# Spectra6PCB_93.net
KiCad netlist of a schematic drawn in EAGLE
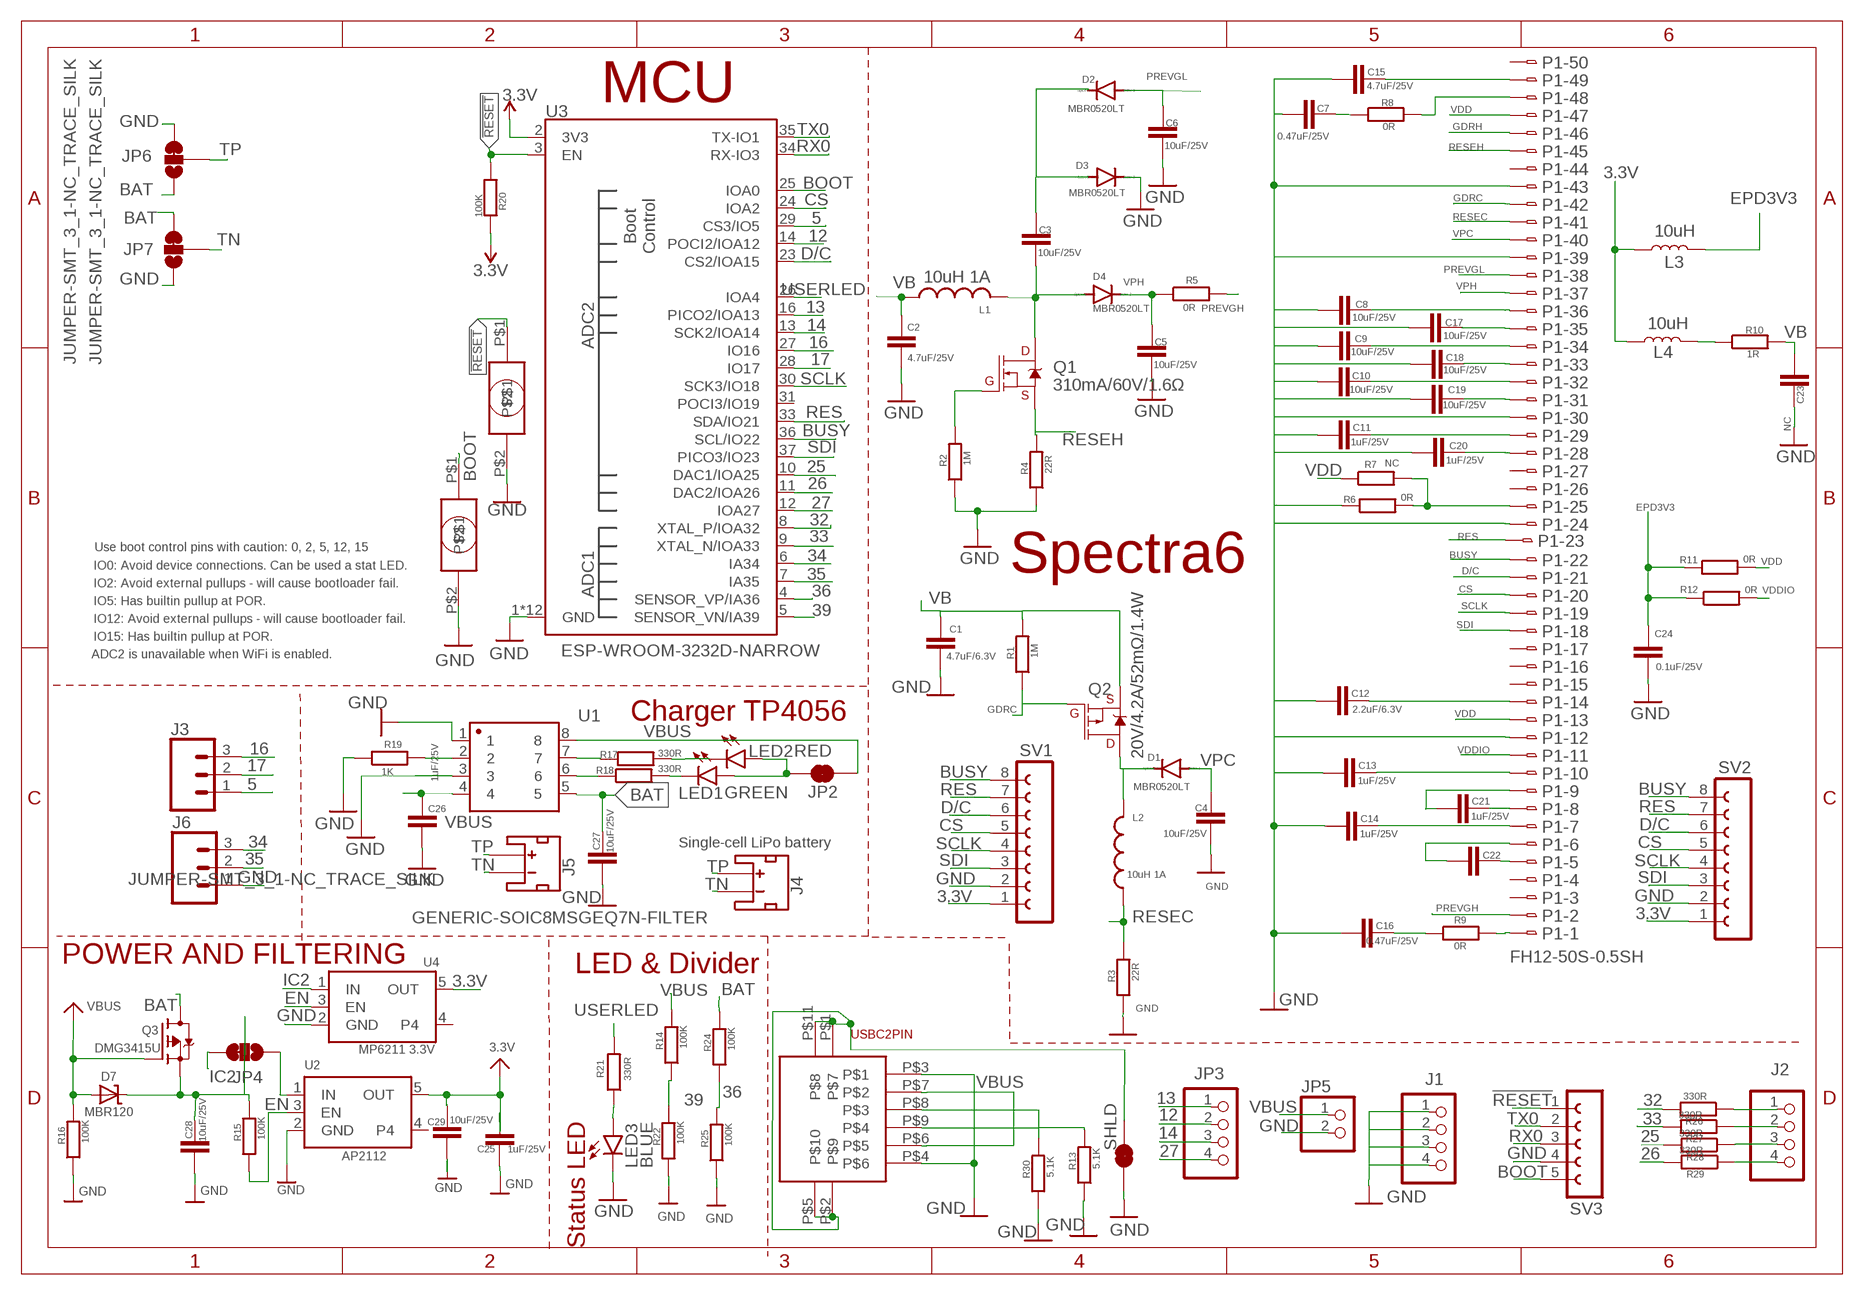
[diagram p0: schematic, sheet 1]

(export (version "E")
  (design (tool "Eeschema 10.0.6"))
  (components
    (comp (ref "C1")
      (value "4.7uF/6.3V")
      (footprint "eagle-import:C0805")
      (libsource (lib "eagle-import") (part "C-EUC0805"))
    )
    (comp (ref "C2")
      (value "4.7uF/25V")
      (footprint "eagle-import:C0805")
      (libsource (lib "eagle-import") (part "C-EUC0805"))
    )
    (comp (ref "C3")
      (value "10uF/25V")
      (footprint "eagle-import:C0805")
      (libsource (lib "eagle-import") (part "C-EUC0805"))
    )
    (comp (ref "C4")
      (value "10uF/25V")
      (footprint "eagle-import:C0805")
      (libsource (lib "eagle-import") (part "C-EUC0805"))
    )
    (comp (ref "C5")
      (value "10uF/25V")
      (footprint "eagle-import:C0805")
      (libsource (lib "eagle-import") (part "C-EUC0805"))
    )
    (comp (ref "C6")
      (value "10uF/25V")
      (footprint "eagle-import:C0805")
      (libsource (lib "eagle-import") (part "C-EUC0805"))
    )
    (comp (ref "C7")
      (value "0.47uF/25V")
      (footprint "eagle-import:C0805")
      (libsource (lib "eagle-import") (part "C-EUC0805"))
    )
    (comp (ref "C8")
      (value "10uF/25V")
      (footprint "eagle-import:C0805")
      (libsource (lib "eagle-import") (part "C-EUC0805"))
    )
    (comp (ref "C9")
      (value "10uF/25V")
      (footprint "eagle-import:C0805")
      (libsource (lib "eagle-import") (part "C-EUC0805"))
    )
    (comp (ref "C10")
      (value "10uF/25V")
      (footprint "eagle-import:C0805")
      (libsource (lib "eagle-import") (part "C-EUC0805"))
    )
    (comp (ref "C11")
      (value "1uF/25V")
      (footprint "eagle-import:C0805")
      (libsource (lib "eagle-import") (part "C-EUC0805"))
    )
    (comp (ref "C12")
      (value "2.2uF/6.3V")
      (footprint "eagle-import:C0805")
      (libsource (lib "eagle-import") (part "C-EUC0805"))
    )
    (comp (ref "C13")
      (value "1uF/25V")
      (footprint "eagle-import:C0805")
      (libsource (lib "eagle-import") (part "C-EUC0805"))
    )
    (comp (ref "C14")
      (value "1uF/25V")
      (footprint "eagle-import:C0805")
      (libsource (lib "eagle-import") (part "C-EUC0805"))
    )
    (comp (ref "C15")
      (value "4.7uF/25V")
      (footprint "eagle-import:C0805")
      (libsource (lib "eagle-import") (part "C-EUC0805"))
    )
    (comp (ref "C16")
      (value "0.47uF/25V")
      (footprint "eagle-import:C0805")
      (libsource (lib "eagle-import") (part "C-EUC0805"))
    )
    (comp (ref "C17")
      (value "10uF/25V")
      (footprint "eagle-import:C0805")
      (libsource (lib "eagle-import") (part "C-EUC0805"))
    )
    (comp (ref "C18")
      (value "10uF/25V")
      (footprint "eagle-import:C0805")
      (libsource (lib "eagle-import") (part "C-EUC0805"))
    )
    (comp (ref "C19")
      (value "10uF/25V")
      (footprint "eagle-import:C0805")
      (libsource (lib "eagle-import") (part "C-EUC0805"))
    )
    (comp (ref "C20")
      (value "1uF/25V")
      (footprint "eagle-import:C0805")
      (libsource (lib "eagle-import") (part "C-EUC0805"))
    )
    (comp (ref "C21")
      (value "1uF/25V")
      (footprint "eagle-import:C0805")
      (libsource (lib "eagle-import") (part "C-EUC0805"))
    )
    (comp (ref "C22")
      (value "1uF/25V")
      (footprint "eagle-import:C0805")
      (libsource (lib "eagle-import") (part "C-EUC0805"))
    )
    (comp (ref "C23")
      (value "NC")
      (footprint "eagle-import:C0805")
      (libsource (lib "eagle-import") (part "C-EUC0805"))
    )
    (comp (ref "C24")
      (value "0.1uF/25V")
      (footprint "eagle-import:C0805")
      (libsource (lib "eagle-import") (part "C-EUC0805"))
    )
    (comp (ref "C25")
      (value "1uF/25V")
      (footprint "eagle-import:C0805")
      (libsource (lib "eagle-import") (part "C-EUC0805"))
    )
    (comp (ref "C26")
      (value "1uF/25V")
      (footprint "eagle-import:C0805")
      (libsource (lib "eagle-import") (part "C-EUC0805"))
    )
    (comp (ref "C27")
      (value "10uF/25V")
      (footprint "eagle-import:C0805")
      (libsource (lib "eagle-import") (part "C-EUC0805"))
    )
    (comp (ref "C28")
      (value "10uF/25V")
      (footprint "eagle-import:C0805")
      (libsource (lib "eagle-import") (part "C-EUC0805"))
    )
    (comp (ref "C29")
      (value "10uF/25V")
      (footprint "eagle-import:C0805")
      (libsource (lib "eagle-import") (part "C-EUC0805"))
    )
    (comp (ref "D1")
      (value "MBR0520LT")
      (footprint "eagle-import:SOD123")
      (libsource (lib "eagle-import") (part "MBR0520LT"))
    )
    (comp (ref "D2")
      (value "MBR0520LT")
      (footprint "eagle-import:SOD123")
      (libsource (lib "eagle-import") (part "MBR0520LT"))
    )
    (comp (ref "D3")
      (value "MBR0520LT")
      (footprint "eagle-import:SOD123")
      (libsource (lib "eagle-import") (part "MBR0520LT"))
    )
    (comp (ref "D4")
      (value "MBR0520LT")
      (footprint "eagle-import:SOD123")
      (libsource (lib "eagle-import") (part "MBR0520LT"))
    )
    (comp (ref "D7")
      (value "MBR120")
      (footprint "eagle-import:SOD-123")
      (libsource (lib "eagle-import") (part "DIODE-SCHOTTKYSOD-123"))
    )
    (comp (ref "J1")
      (value "PINHD-1X4")
      (footprint "eagle-import:1X04")
      (libsource (lib "eagle-import") (part "PINHD-1X4"))
    )
    (comp (ref "J2")
      (value "PINHD-1X4")
      (footprint "eagle-import:1X04")
      (libsource (lib "eagle-import") (part "PINHD-1X4"))
    )
    (comp (ref "J3")
      (value "CONN_03PAD")
      (footprint "eagle-import:1X03_SOLDER_PADS")
      (libsource (lib "eagle-import") (part "CONN_03PAD"))
    )
    (comp (ref "J4")
      (value "JST_2MM_MALE")
      (footprint "eagle-import:JST-2-SMD")
      (libsource (lib "eagle-import") (part "JST_2MM_MALE"))
    )
    (comp (ref "J5")
      (value "NC")
      (footprint "eagle-import:JST-2-SMD")
      (libsource (lib "eagle-import") (part "JST_2MM_MALE"))
    )
    (comp (ref "J6")
      (value "CONN_03PAD")
      (footprint "eagle-import:1X03_SOLDER_PADS")
      (libsource (lib "eagle-import") (part "CONN_03PAD"))
    )
    (comp (ref "JP2")
      (value "JUMPER-SMT_2_NC_TRACE_SILK")
      (footprint "eagle-import:SMT-JUMPER_2_NC_TRACE_SILK")
      (libsource (lib "eagle-import") (part "JUMPER-SMT_2_NC_TRACE_SILK"))
    )
    (comp (ref "JP3")
      (value "PINHD-1X4")
      (footprint "eagle-import:1X04")
      (libsource (lib "eagle-import") (part "PINHD-1X4"))
    )
    (comp (ref "JP4")
      (value "JUMPER-SMT_3_1-NC_TRACE_SILK")
      (footprint "eagle-import:SMT-JUMPER_3_1-NC_TRACE_SILK")
      (libsource (lib "eagle-import") (part "JUMPER-SMT_3_1-NC_TRACE_SILK"))
    )
    (comp (ref "JP5")
      (value "PINHD-1X2")
      (footprint "eagle-import:1X02")
      (libsource (lib "eagle-import") (part "PINHD-1X2"))
    )
    (comp (ref "JP6")
      (value "JUMPER-SMT_3_1-NC_TRACE_SILK")
      (footprint "eagle-import:SMT-JUMPER_3_1-NC_TRACE_SILK")
      (libsource (lib "eagle-import") (part "JUMPER-SMT_3_1-NC_TRACE_SILK"))
    )
    (comp (ref "JP7")
      (value "JUMPER-SMT_3_1-NC_TRACE_SILK")
      (footprint "eagle-import:SMT-JUMPER_3_1-NC_TRACE_SILK")
      (libsource (lib "eagle-import") (part "JUMPER-SMT_3_1-NC_TRACE_SILK"))
    )
    (comp (ref "L1")
      (value "10uH 1A")
      (footprint "eagle-import:L4035M")
      (libsource (lib "eagle-import") (part "L-USL4035M"))
    )
    (comp (ref "L2")
      (value "10uH 1A")
      (footprint "eagle-import:L4035M")
      (libsource (lib "eagle-import") (part "L-USL4035M"))
    )
    (comp (ref "L3")
      (value "10uH")
      (footprint "eagle-import:0805")
      (libsource (lib "eagle-import") (part "INDUCTOR-0805-3.3UH"))
    )
    (comp (ref "L4")
      (value "10uH")
      (footprint "eagle-import:0805")
      (libsource (lib "eagle-import") (part "INDUCTOR-0805-3.3UH"))
    )
    (comp (ref "LED1")
      (value "GREEN")
      (footprint "eagle-import:SML0805")
      (libsource (lib "eagle-import") (part "LEDSML0805"))
    )
    (comp (ref "LED2")
      (value "RED")
      (footprint "eagle-import:SML0805")
      (libsource (lib "eagle-import") (part "LEDSML0805"))
    )
    (comp (ref "LED3")
      (value "BLUE")
      (footprint "eagle-import:SML0805")
      (libsource (lib "eagle-import") (part "LEDSML0805"))
    )
    (comp (ref "P1")
      (value "FH12-50S-0.5SH")
      (footprint "eagle-import:FH12-50S-0.5SH")
      (fields (field (name "MPN") "FH12-50S-0.5SH(55)"))
      (libsource (lib "eagle-import") (part "FH12-50S-0.5SH"))
    )
    (comp (ref "Q1")
      (value "310mA/60V/1.6Ω")
      (footprint "eagle-import:SOT323")
      (libsource (lib "eagle-import") (part "MOSFET-NCH-2N7002PW"))
    )
    (comp (ref "Q2")
      (value "20V/4.2A/52mΩ/1.4W")
      (footprint "eagle-import:SOT23-3")
      (libsource (lib "eagle-import") (part "MOSFET_PCH-DMG2305UX-7"))
    )
    (comp (ref "Q3")
      (value "DMG3415U")
      (footprint "eagle-import:SOT23-R")
      (libsource (lib "eagle-import") (part "MOSFET-P"))
    )
    (comp (ref "R1")
      (value "1M")
      (footprint "eagle-import:M0805")
      (libsource (lib "eagle-import") (part "R-EU_M0805"))
    )
    (comp (ref "R2")
      (value "1M")
      (footprint "eagle-import:M0805")
      (libsource (lib "eagle-import") (part "R-EU_M0805"))
    )
    (comp (ref "R3")
      (value "22R")
      (footprint "eagle-import:M0805")
      (libsource (lib "eagle-import") (part "R-EU_M0805"))
    )
    (comp (ref "R4")
      (value "22R")
      (footprint "eagle-import:M0805")
      (libsource (lib "eagle-import") (part "R-EU_M0805"))
    )
    (comp (ref "R5")
      (value "0R")
      (footprint "eagle-import:M0805")
      (libsource (lib "eagle-import") (part "R-EU_M0805"))
    )
    (comp (ref "R6")
      (value "0R")
      (footprint "eagle-import:M0805")
      (libsource (lib "eagle-import") (part "R-EU_M0805"))
    )
    (comp (ref "R7")
      (value "NC")
      (footprint "eagle-import:M0805")
      (libsource (lib "eagle-import") (part "R-EU_M0805"))
    )
    (comp (ref "R8")
      (value "0R")
      (footprint "eagle-import:M0805")
      (libsource (lib "eagle-import") (part "R-EU_M0805"))
    )
    (comp (ref "R9")
      (value "0R")
      (footprint "eagle-import:M0805")
      (libsource (lib "eagle-import") (part "R-EU_M0805"))
    )
    (comp (ref "R10")
      (value "1R")
      (footprint "eagle-import:M0805")
      (libsource (lib "eagle-import") (part "R-EU_M0805"))
    )
    (comp (ref "R11")
      (value "0R")
      (footprint "eagle-import:M0805")
      (libsource (lib "eagle-import") (part "R-EU_M0805"))
    )
    (comp (ref "R12")
      (value "0R")
      (footprint "eagle-import:M0805")
      (libsource (lib "eagle-import") (part "R-EU_M0805"))
    )
    (comp (ref "R13")
      (value "5.1K")
      (footprint "eagle-import:M0805")
      (libsource (lib "eagle-import") (part "R-EU_M0805"))
    )
    (comp (ref "R14")
      (value "100K")
      (footprint "eagle-import:M0805")
      (libsource (lib "eagle-import") (part "R-EU_M0805"))
    )
    (comp (ref "R15")
      (value "100K")
      (footprint "eagle-import:M0805")
      (libsource (lib "eagle-import") (part "R-EU_M0805"))
    )
    (comp (ref "R16")
      (value "100K")
      (footprint "eagle-import:M0805")
      (libsource (lib "eagle-import") (part "R-EU_M0805"))
    )
    (comp (ref "R17")
      (value "330R")
      (footprint "eagle-import:M0805")
      (libsource (lib "eagle-import") (part "R-EU_M0805"))
    )
    (comp (ref "R18")
      (value "330R")
      (footprint "eagle-import:M0805")
      (libsource (lib "eagle-import") (part "R-EU_M0805"))
    )
    (comp (ref "R19")
      (value "1K")
      (footprint "eagle-import:M0805")
      (libsource (lib "eagle-import") (part "R-EU_M0805"))
    )
    (comp (ref "R20")
      (value "100K")
      (footprint "eagle-import:M0805")
      (libsource (lib "eagle-import") (part "R-EU_M0805"))
    )
    (comp (ref "R21")
      (value "330R")
      (footprint "eagle-import:M0805")
      (libsource (lib "eagle-import") (part "R-EU_M0805"))
    )
    (comp (ref "R22")
      (value "100K")
      (footprint "eagle-import:M0805")
      (libsource (lib "eagle-import") (part "R-EU_M0805"))
    )
    (comp (ref "R24")
      (value "100K")
      (footprint "eagle-import:M0805")
      (libsource (lib "eagle-import") (part "R-EU_M0805"))
    )
    (comp (ref "R25")
      (value "100K")
      (footprint "eagle-import:M0805")
      (libsource (lib "eagle-import") (part "R-EU_M0805"))
    )
    (comp (ref "R26")
      (value "330R")
      (footprint "eagle-import:M0805")
      (libsource (lib "eagle-import") (part "R-EU_M0805"))
    )
    (comp (ref "R27")
      (value "330R")
      (footprint "eagle-import:M0805")
      (libsource (lib "eagle-import") (part "R-EU_M0805"))
    )
    (comp (ref "R28")
      (value "330R")
      (footprint "eagle-import:M0805")
      (libsource (lib "eagle-import") (part "R-EU_M0805"))
    )
    (comp (ref "R29")
      (value "330R")
      (footprint "eagle-import:M0805")
      (libsource (lib "eagle-import") (part "R-EU_M0805"))
    )
    (comp (ref "R30")
      (value "5.1K")
      (footprint "eagle-import:M0805")
      (libsource (lib "eagle-import") (part "R-EU_M0805"))
    )
    (comp (ref "S3")
      (value "TACTILE")
      (footprint "eagle-import:TACTILE")
      (libsource (lib "eagle-import") (part "TACTILE"))
    )
    (comp (ref "S4")
      (value "TACTILE")
      (footprint "eagle-import:TACTILE")
      (libsource (lib "eagle-import") (part "TACTILE"))
    )
    (comp (ref "SHLD")
      (value "SHLD")
      (footprint "eagle-import:SMT-JUMPER_2_NC_TRACE_NO-SILK")
      (libsource (lib "eagle-import") (part "JUMPER-SMT_2_NC_TRACE_NO-SILK"))
    )
    (comp (ref "SV1")
      (value "FE08-1")
      (footprint "eagle-import:FE08")
      (libsource (lib "eagle-import") (part "FE08-1"))
    )
    (comp (ref "SV2")
      (value "FE08-1")
      (footprint "eagle-import:FE08")
      (libsource (lib "eagle-import") (part "FE08-1"))
    )
    (comp (ref "SV3")
      (value "FE05-1")
      (footprint "eagle-import:FE05-1")
      (libsource (lib "eagle-import") (part "FE05-1"))
    )
    (comp (ref "U$4")
      (value "USBC6PIN")
      (footprint "eagle-import:USBC6PIN")
      (libsource (lib "eagle-import") (part "USBC6PIN"))
    )
    (comp (ref "U1")
      (value "GENERIC-SOIC8MSGEQ7N-FILTER")
      (footprint "eagle-import:SO08")
      (libsource (lib "eagle-import") (part "GENERIC-SOIC8MSGEQ7N-FILTER"))
    )
    (comp (ref "U2")
      (value "AP2112")
      (footprint "eagle-import:SOT23-5")
      (libsource (lib "eagle-import") (part "VREG_SOT23-5"))
    )
    (comp (ref "U3")
      (value "ESP-WROOM-3232D-NARROW")
      (footprint "eagle-import:ESP-WROOM-32D-NARROW")
      (libsource (lib "eagle-import") (part "ESP-WROOM-3232D-NARROW"))
    )
    (comp (ref "U4")
      (value "MP6211 3.3V")
      (footprint "eagle-import:SOT23-5")
      (libsource (lib "eagle-import") (part "VREG_SOT23-5"))
    )
  )
  (nets
    (net (code "1") (name "/5") (class "Default")
      (node (ref "J3") (pin "1") (pinfunction "1_1") (pintype "passive"))
      (node (ref "U3") (pin "29") (pinfunction "CS3/IO5_29") (pintype "bidirectional"))
    )
    (net (code "2") (name "/12") (class "Default")
      (node (ref "JP3") (pin "2") (pinfunction "2_2") (pintype "passive"))
      (node (ref "U3") (pin "14") (pinfunction "POCI2/IOA12_14") (pintype "bidirectional"))
    )
    (net (code "3") (name "/13") (class "Default")
      (node (ref "JP3") (pin "1") (pinfunction "1_1") (pintype "passive"))
      (node (ref "U3") (pin "16") (pinfunction "PICO2/IOA13_16") (pintype "bidirectional"))
    )
    (net (code "4") (name "/14") (class "Default")
      (node (ref "JP3") (pin "3") (pinfunction "3_3") (pintype "passive"))
      (node (ref "U3") (pin "13") (pinfunction "SCK2/IOA14_13") (pintype "bidirectional"))
    )
    (net (code "5") (name "/16") (class "Default")
      (node (ref "J3") (pin "3") (pinfunction "3_3") (pintype "passive"))
      (node (ref "U3") (pin "27") (pinfunction "IO16_27") (pintype "bidirectional"))
    )
    (net (code "6") (name "/17") (class "Default")
      (node (ref "J3") (pin "2") (pinfunction "2_2") (pintype "passive"))
      (node (ref "U3") (pin "28") (pinfunction "IO17_28") (pintype "bidirectional"))
    )
    (net (code "7") (name "/25") (class "Default")
      (node (ref "R28") (pin "2") (pinfunction "2_2") (pintype "passive"))
      (node (ref "U3") (pin "10") (pinfunction "DAC1/IOA25_10") (pintype "bidirectional"))
    )
    (net (code "8") (name "/26") (class "Default")
      (node (ref "R29") (pin "2") (pinfunction "2_2") (pintype "passive"))
      (node (ref "U3") (pin "11") (pinfunction "DAC2/IOA26_11") (pintype "bidirectional"))
    )
    (net (code "9") (name "/27") (class "Default")
      (node (ref "JP3") (pin "4") (pinfunction "4_4") (pintype "passive"))
      (node (ref "U3") (pin "12") (pinfunction "IOA27_12") (pintype "bidirectional"))
    )
    (net (code "10") (name "/32") (class "Default")
      (node (ref "R26") (pin "2") (pinfunction "2_2") (pintype "passive"))
      (node (ref "U3") (pin "8") (pinfunction "XTAL_P/IOA32_8") (pintype "bidirectional"))
    )
    (net (code "11") (name "/33") (class "Default")
      (node (ref "R27") (pin "2") (pinfunction "2_2") (pintype "passive"))
      (node (ref "U3") (pin "9") (pinfunction "XTAL_N/IOA33_9") (pintype "bidirectional"))
    )
    (net (code "12") (name "/34") (class "Default")
      (node (ref "J6") (pin "3") (pinfunction "3_3") (pintype "passive"))
      (node (ref "U3") (pin "6") (pinfunction "IA34_6") (pintype "bidirectional"))
    )
    (net (code "13") (name "/35") (class "Default")
      (node (ref "J6") (pin "2") (pinfunction "2_2") (pintype "passive"))
      (node (ref "U3") (pin "7") (pinfunction "IA35_7") (pintype "bidirectional"))
    )
    (net (code "14") (name "/36") (class "Default")
      (node (ref "R24") (pin "1") (pinfunction "1_1") (pintype "passive"))
      (node (ref "R25") (pin "2") (pinfunction "2_2") (pintype "passive"))
      (node (ref "U3") (pin "4") (pinfunction "SENSOR_VP/IA36_4") (pintype "bidirectional"))
    )
    (net (code "15") (name "/39") (class "Default")
      (node (ref "R14") (pin "1") (pinfunction "1_1") (pintype "passive"))
      (node (ref "R22") (pin "2") (pinfunction "2_2") (pintype "passive"))
      (node (ref "U3") (pin "5") (pinfunction "SENSOR_VN/IA39_5") (pintype "bidirectional"))
    )
    (net (code "16") (name "/BOOT") (class "Default")
      (node (ref "S3") (pin "P$1") (pinfunction "P$1_P$1") (pintype "bidirectional"))
      (node (ref "SV3") (pin "5") (pinfunction "5_5") (pintype "passive"))
      (node (ref "U3") (pin "25") (pinfunction "IOA0_25") (pintype "bidirectional"))
    )
    (net (code "17") (name "/BUSY") (class "Default")
      (node (ref "P1") (pin "22") (pinfunction "1_22") (pintype "passive"))
      (node (ref "SV1") (pin "8") (pinfunction "8_8") (pintype "passive"))
      (node (ref "SV2") (pin "8") (pinfunction "8_8") (pintype "passive"))
      (node (ref "U3") (pin "36") (pinfunction "SCL/IO22_36") (pintype "bidirectional"))
    )
    (net (code "18") (name "/CS") (class "Default")
      (node (ref "P1") (pin "20") (pinfunction "1_20") (pintype "passive"))
      (node (ref "SV1") (pin "5") (pinfunction "5_5") (pintype "passive"))
      (node (ref "SV2") (pin "5") (pinfunction "5_5") (pintype "passive"))
      (node (ref "U3") (pin "24") (pinfunction "IOA2_24") (pintype "bidirectional"))
    )
    (net (code "19") (name "/D{slash}C") (class "Default")
      (node (ref "P1") (pin "21") (pinfunction "1_21") (pintype "passive"))
      (node (ref "SV1") (pin "6") (pinfunction "6_6") (pintype "passive"))
      (node (ref "SV2") (pin "6") (pinfunction "6_6") (pintype "passive"))
      (node (ref "U3") (pin "23") (pinfunction "CS2/IOA15_23") (pintype "bidirectional"))
    )
    (net (code "20") (name "/EN") (class "Default")
      (node (ref "R15") (pin "1") (pinfunction "1_1") (pintype "passive"))
      (node (ref "U2") (pin "3") (pinfunction "EN_3") (pintype "input"))
      (node (ref "U4") (pin "3") (pinfunction "EN_3") (pintype "input"))
    )
    (net (code "21") (name "/EPD3V3") (class "Default")
      (node (ref "C24") (pin "2") (pinfunction "2_2") (pintype "passive"))
      (node (ref "L3") (pin "2") (pinfunction "2_2") (pintype "passive"))
      (node (ref "R11") (pin "1") (pinfunction "1_1") (pintype "passive"))
      (node (ref "R12") (pin "1") (pinfunction "1_1") (pintype "passive"))
    )
    (net (code "22") (name "/GDRC") (class "Default")
      (node (ref "P1") (pin "42") (pinfunction "1_42") (pintype "passive"))
      (node (ref "Q2") (pin "1") (pinfunction "G_1") (pintype "bidirectional"))
      (node (ref "R1") (pin "1") (pinfunction "1_1") (pintype "passive"))
    )
    (net (code "23") (name "/GDRH") (class "Default")
      (node (ref "P1") (pin "46") (pinfunction "1_46") (pintype "passive"))
      (node (ref "Q1") (pin "1") (pinfunction "G_1") (pintype "bidirectional"))
      (node (ref "R2") (pin "2") (pinfunction "2_2") (pintype "passive"))
    )
    (net (code "24") (name "/IC2") (class "Default")
      (node (ref "JP4") (pin "3") (pinfunction "3_3") (pintype "passive"))
      (node (ref "U4") (pin "1") (pinfunction "IN_1") (pintype "power_in"))
    )
    (net (code "25") (name "/PREVGH") (class "Default")
      (node (ref "P1") (pin "2") (pinfunction "1_2") (pintype "passive"))
      (node (ref "R5") (pin "2") (pinfunction "2_2") (pintype "passive"))
    )
    (net (code "26") (name "/PREVGL") (class "Default")
      (node (ref "C6") (pin "1") (pinfunction "1_1") (pintype "passive"))
      (node (ref "D2") (pin "A") (pinfunction "A_A") (pintype "passive"))
      (node (ref "P1") (pin "38") (pinfunction "1_38") (pintype "passive"))
    )
    (net (code "27") (name "/RES") (class "Default")
      (node (ref "P1") (pin "23") (pinfunction "1_23") (pintype "passive"))
      (node (ref "SV1") (pin "7") (pinfunction "7_7") (pintype "passive"))
      (node (ref "SV2") (pin "7") (pinfunction "7_7") (pintype "passive"))
      (node (ref "U3") (pin "33") (pinfunction "SDA/IO21_33") (pintype "bidirectional"))
    )
    (net (code "28") (name "/RESEC") (class "Default")
      (node (ref "L2") (pin "1") (pinfunction "1_1") (pintype "passive"))
      (node (ref "P1") (pin "41") (pinfunction "1_41") (pintype "passive"))
      (node (ref "R3") (pin "2") (pinfunction "2_2") (pintype "passive"))
    )
    (net (code "29") (name "/RESEH") (class "Default")
      (node (ref "P1") (pin "45") (pinfunction "1_45") (pintype "passive"))
      (node (ref "Q1") (pin "2") (pinfunction "S_2") (pintype "bidirectional"))
      (node (ref "R4") (pin "2") (pinfunction "2_2") (pintype "passive"))
    )
    (net (code "30") (name "/RX0") (class "Default")
      (node (ref "SV3") (pin "3") (pinfunction "3_3") (pintype "passive"))
      (node (ref "U3") (pin "34") (pinfunction "RX-IO3_34") (pintype "bidirectional"))
    )
    (net (code "31") (name "/SCLK") (class "Default")
      (node (ref "P1") (pin "19") (pinfunction "1_19") (pintype "passive"))
      (node (ref "SV1") (pin "4") (pinfunction "4_4") (pintype "passive"))
      (node (ref "SV2") (pin "4") (pinfunction "4_4") (pintype "passive"))
      (node (ref "U3") (pin "30") (pinfunction "SCK3/IO18_30") (pintype "bidirectional"))
    )
    (net (code "32") (name "/SDI") (class "Default")
      (node (ref "P1") (pin "18") (pinfunction "1_18") (pintype "passive"))
      (node (ref "SV1") (pin "3") (pinfunction "3_3") (pintype "passive"))
      (node (ref "SV2") (pin "3") (pinfunction "3_3") (pintype "passive"))
      (node (ref "U3") (pin "37") (pinfunction "PICO3/IO23_37") (pintype "bidirectional"))
    )
    (net (code "33") (name "/TN") (class "Default")
      (node (ref "J4") (pin "1") (pinfunction "-_1") (pintype "bidirectional"))
      (node (ref "J5") (pin "1") (pinfunction "-_1") (pintype "bidirectional"))
      (node (ref "JP7") (pin "2") (pinfunction "2_2") (pintype "passive"))
    )
    (net (code "34") (name "/TP") (class "Default")
      (node (ref "J4") (pin "2") (pinfunction "+_2") (pintype "bidirectional"))
      (node (ref "J5") (pin "2") (pinfunction "+_2") (pintype "bidirectional"))
      (node (ref "JP6") (pin "2") (pinfunction "2_2") (pintype "passive"))
    )
    (net (code "35") (name "/TX0") (class "Default")
      (node (ref "SV3") (pin "2") (pinfunction "2_2") (pintype "passive"))
      (node (ref "U3") (pin "35") (pinfunction "TX-IO1_35") (pintype "bidirectional"))
    )
    (net (code "36") (name "/USERLED") (class "Default")
      (node (ref "R21") (pin "2") (pinfunction "2_2") (pintype "passive"))
      (node (ref "U3") (pin "26") (pinfunction "IOA4_26") (pintype "bidirectional"))
    )
    (net (code "37") (name "/VB") (class "Default")
      (node (ref "C2") (pin "2") (pinfunction "2_2") (pintype "passive"))
      (node (ref "C23") (pin "1") (pinfunction "1_1") (pintype "passive"))
      (node (ref "L1") (pin "1") (pinfunction "1_1") (pintype "passive"))
      (node (ref "R10") (pin "2") (pinfunction "2_2") (pintype "passive"))
    )
    (net (code "38") (name "/VDD") (class "Default")
      (node (ref "P1") (pin "13") (pinfunction "1_13") (pintype "passive"))
      (node (ref "P1") (pin "47") (pinfunction "1_47") (pintype "passive"))
      (node (ref "R11") (pin "2") (pinfunction "2_2") (pintype "passive"))
      (node (ref "R7") (pin "1") (pinfunction "1_1") (pintype "passive"))
    )
    (net (code "39") (name "/VDDIO") (class "Default")
      (node (ref "P1") (pin "11") (pinfunction "1_11") (pintype "passive"))
      (node (ref "R12") (pin "2") (pinfunction "2_2") (pintype "passive"))
    )
    (net (code "40") (name "/VPC") (class "Default")
      (node (ref "C4") (pin "2") (pinfunction "2_2") (pintype "passive"))
      (node (ref "D1") (pin "A") (pinfunction "A_A") (pintype "passive"))
      (node (ref "P1") (pin "40") (pinfunction "1_40") (pintype "passive"))
    )
    (net (code "41") (name "/VPH") (class "Default")
      (node (ref "C5") (pin "1") (pinfunction "1_1") (pintype "passive"))
      (node (ref "D4") (pin "C") (pinfunction "C_C") (pintype "passive"))
      (node (ref "P1") (pin "37") (pinfunction "1_37") (pintype "passive"))
      (node (ref "R5") (pin "1") (pinfunction "1_1") (pintype "passive"))
    )
    (net (code "42") (name "/~{RESET}") (class "Default")
      (node (ref "R20") (pin "1") (pinfunction "1_1") (pintype "passive"))
      (node (ref "S4") (pin "P$1") (pinfunction "P$1_P$1") (pintype "bidirectional"))
      (node (ref "SV3") (pin "1") (pinfunction "1_1") (pintype "passive"))
      (node (ref "U3") (pin "3") (pinfunction "EN_3") (pintype "bidirectional"))
    )
    (net (code "43") (name "3.3V") (class "Default")
      (node (ref "C25") (pin "2") (pinfunction "2_2") (pintype "passive"))
      (node (ref "C29") (pin "2") (pinfunction "2_2") (pintype "passive"))
      (node (ref "L3") (pin "1") (pinfunction "1_1") (pintype "passive"))
      (node (ref "L4") (pin "1") (pinfunction "1_1") (pintype "passive"))
      (node (ref "R20") (pin "2") (pinfunction "2_2") (pintype "passive"))
      (node (ref "SV1") (pin "1") (pinfunction "1_1") (pintype "passive"))
      (node (ref "SV2") (pin "1") (pinfunction "1_1") (pintype "passive"))
      (node (ref "U2") (pin "5") (pinfunction "OUT_5") (pintype "power_in"))
      (node (ref "U3") (pin "2") (pinfunction "3V3_2") (pintype "bidirectional"))
      (node (ref "U4") (pin "5") (pinfunction "OUT_5") (pintype "power_in"))
    )
    (net (code "44") (name "BAT") (class "Default")
      (node (ref "C27") (pin "2") (pinfunction "2_2") (pintype "passive"))
      (node (ref "JP6") (pin "1") (pinfunction "1_1") (pintype "passive"))
      (node (ref "JP7") (pin "3") (pinfunction "3_3") (pintype "passive"))
      (node (ref "Q3") (pin "3") (pinfunction "D_3") (pintype "passive"))
      (node (ref "R24") (pin "2") (pinfunction "2_2") (pintype "passive"))
      (node (ref "U1") (pin "5") (pinfunction "5_5") (pintype "bidirectional"))
    )
    (net (code "45") (name "GND") (class "Default")
      (node (ref "C1") (pin "1") (pinfunction "1_1") (pintype "passive"))
      (node (ref "C10") (pin "1") (pinfunction "1_1") (pintype "passive"))
      (node (ref "C11") (pin "1") (pinfunction "1_1") (pintype "passive"))
      (node (ref "C12") (pin "1") (pinfunction "1_1") (pintype "passive"))
      (node (ref "C13") (pin "1") (pinfunction "1_1") (pintype "passive"))
      (node (ref "C14") (pin "1") (pinfunction "1_1") (pintype "passive"))
      (node (ref "C15") (pin "1") (pinfunction "1_1") (pintype "passive"))
      (node (ref "C16") (pin "1") (pinfunction "1_1") (pintype "passive"))
      (node (ref "C17") (pin "1") (pinfunction "1_1") (pintype "passive"))
      (node (ref "C18") (pin "1") (pinfunction "1_1") (pintype "passive"))
      (node (ref "C19") (pin "1") (pinfunction "1_1") (pintype "passive"))
      (node (ref "C2") (pin "1") (pinfunction "1_1") (pintype "passive"))
      (node (ref "C20") (pin "1") (pinfunction "1_1") (pintype "passive"))
      (node (ref "C23") (pin "2") (pinfunction "2_2") (pintype "passive"))
      (node (ref "C24") (pin "1") (pinfunction "1_1") (pintype "passive"))
      (node (ref "C25") (pin "1") (pinfunction "1_1") (pintype "passive"))
      (node (ref "C26") (pin "1") (pinfunction "1_1") (pintype "passive"))
      (node (ref "C27") (pin "1") (pinfunction "1_1") (pintype "passive"))
      (node (ref "C28") (pin "1") (pinfunction "1_1") (pintype "passive"))
      (node (ref "C29") (pin "1") (pinfunction "1_1") (pintype "passive"))
      (node (ref "C4") (pin "1") (pinfunction "1_1") (pintype "passive"))
      (node (ref "C5") (pin "2") (pinfunction "2_2") (pintype "passive"))
      (node (ref "C6") (pin "2") (pinfunction "2_2") (pintype "passive"))
      (node (ref "C7") (pin "1") (pinfunction "1_1") (pintype "passive"))
      (node (ref "C8") (pin "1") (pinfunction "1_1") (pintype "passive"))
      (node (ref "C9") (pin "1") (pinfunction "1_1") (pintype "passive"))
      (node (ref "D3") (pin "C") (pinfunction "C_C") (pintype "passive"))
      (node (ref "J1") (pin "1") (pinfunction "1_1") (pintype "passive"))
      (node (ref "J1") (pin "2") (pinfunction "2_2") (pintype "passive"))
      (node (ref "J1") (pin "3") (pinfunction "3_3") (pintype "passive"))
      (node (ref "J1") (pin "4") (pinfunction "4_4") (pintype "passive"))
      (node (ref "J6") (pin "1") (pinfunction "1_1") (pintype "passive"))
      (node (ref "JP5") (pin "2") (pinfunction "2_2") (pintype "passive"))
      (node (ref "JP6") (pin "3") (pinfunction "3_3") (pintype "passive"))
      (node (ref "JP7") (pin "1") (pinfunction "1_1") (pintype "passive"))
      (node (ref "LED3") (pin "C") (pinfunction "C_C") (pintype "passive"))
      (node (ref "P1") (pin "24") (pinfunction "1_24") (pintype "passive"))
      (node (ref "P1") (pin "30") (pinfunction "1_30") (pintype "passive"))
      (node (ref "P1") (pin "39") (pinfunction "1_39") (pintype "passive"))
      (node (ref "P1") (pin "43") (pinfunction "1_43") (pintype "passive"))
      (node (ref "R13") (pin "1") (pinfunction "1_1") (pintype "passive"))
      (node (ref "R16") (pin "1") (pinfunction "1_1") (pintype "passive"))
      (node (ref "R19") (pin "1") (pinfunction "1_1") (pintype "passive"))
      (node (ref "R2") (pin "1") (pinfunction "1_1") (pintype "passive"))
      (node (ref "R22") (pin "1") (pinfunction "1_1") (pintype "passive"))
      (node (ref "R25") (pin "1") (pinfunction "1_1") (pintype "passive"))
      (node (ref "R3") (pin "1") (pinfunction "1_1") (pintype "passive"))
      (node (ref "R30") (pin "1") (pinfunction "1_1") (pintype "passive"))
      (node (ref "R4") (pin "1") (pinfunction "1_1") (pintype "passive"))
      (node (ref "R6") (pin "1") (pinfunction "1_1") (pintype "passive"))
      (node (ref "S3") (pin "P$2") (pinfunction "P$2_P$2") (pintype "bidirectional"))
      (node (ref "S4") (pin "P$2") (pinfunction "P$2_P$2") (pintype "bidirectional"))
      (node (ref "SHLD") (pin "1") (pinfunction "1_1") (pintype "passive"))
      (node (ref "SV1") (pin "2") (pinfunction "2_2") (pintype "passive"))
      (node (ref "SV2") (pin "2") (pinfunction "2_2") (pintype "passive"))
      (node (ref "SV3") (pin "4") (pinfunction "4_4") (pintype "passive"))
      (node (ref "U$4") (pin "P$3") (pinfunction "P$1_P$3") (pintype "bidirectional"))
      (node (ref "U$4") (pin "P$4") (pinfunction "P$6_P$4") (pintype "bidirectional"))
      (node (ref "U1") (pin "1") (pinfunction "1_1") (pintype "bidirectional"))
      (node (ref "U1") (pin "3") (pinfunction "3_3") (pintype "bidirectional"))
      (node (ref "U2") (pin "2") (pinfunction "GND_2") (pintype "power_in"))
      (node (ref "U3") (pin "1") (pinfunction "GND_1") (pintype "bidirectional"))
      (node (ref "U3") (pin "15") (pinfunction "GND_15") (pintype "bidirectional"))
      (node (ref "U3") (pin "38") (pinfunction "GND_38") (pintype "bidirectional"))
      (node (ref "U3") (pin "GND1") (pinfunction "GND_GND1") (pintype "bidirectional"))
      (node (ref "U3") (pin "GNDT1") (pinfunction "GND_GNDT1") (pintype "bidirectional"))
      (node (ref "U3") (pin "GNDT2") (pinfunction "GND_GNDT2") (pintype "bidirectional"))
      (node (ref "U3") (pin "GNDT3") (pinfunction "GND_GNDT3") (pintype "bidirectional"))
      (node (ref "U3") (pin "GNDT4") (pinfunction "GND_GNDT4") (pintype "bidirectional"))
      (node (ref "U3") (pin "GNDT5") (pinfunction "GND_GNDT5") (pintype "bidirectional"))
      (node (ref "U3") (pin "GNDT6") (pinfunction "GND_GNDT6") (pintype "bidirectional"))
      (node (ref "U3") (pin "GNDT7") (pinfunction "GND_GNDT7") (pintype "bidirectional"))
      (node (ref "U3") (pin "GNDT8") (pinfunction "GND_GNDT8") (pintype "bidirectional"))
      (node (ref "U4") (pin "2") (pinfunction "GND_2") (pintype "power_in"))
    )
    (net (code "46") (name "Net-(C3-Pad1)") (class "Default")
      (node (ref "C3") (pin "1") (pinfunction "1_1") (pintype "passive"))
      (node (ref "D2") (pin "C") (pinfunction "C_C") (pintype "passive"))
      (node (ref "D3") (pin "A") (pinfunction "A_A") (pintype "passive"))
    )
    (net (code "47") (name "Net-(C7-Pad2)") (class "Default")
      (node (ref "C7") (pin "2") (pinfunction "2_2") (pintype "passive"))
      (node (ref "R8") (pin "1") (pinfunction "1_1") (pintype "passive"))
    )
    (net (code "48") (name "Net-(C16-Pad2)") (class "Default")
      (node (ref "C16") (pin "2") (pinfunction "2_2") (pintype "passive"))
      (node (ref "R9") (pin "1") (pinfunction "1_1") (pintype "passive"))
    )
    (net (code "49") (name "Net-(J2-Pad1)") (class "Default")
      (node (ref "J2") (pin "1") (pinfunction "1_1") (pintype "passive"))
      (node (ref "R26") (pin "1") (pinfunction "1_1") (pintype "passive"))
    )
    (net (code "50") (name "Net-(J2-Pad2)") (class "Default")
      (node (ref "J2") (pin "2") (pinfunction "2_2") (pintype "passive"))
      (node (ref "R27") (pin "1") (pinfunction "1_1") (pintype "passive"))
    )
    (net (code "51") (name "Net-(J2-Pad3)") (class "Default")
      (node (ref "J2") (pin "3") (pinfunction "3_3") (pintype "passive"))
      (node (ref "R28") (pin "1") (pinfunction "1_1") (pintype "passive"))
    )
    (net (code "52") (name "Net-(J2-Pad4)") (class "Default")
      (node (ref "J2") (pin "4") (pinfunction "4_4") (pintype "passive"))
      (node (ref "R29") (pin "1") (pinfunction "1_1") (pintype "passive"))
    )
    (net (code "53") (name "Net-(JP2-Pad2)") (class "Default")
      (node (ref "JP2") (pin "2") (pinfunction "2_2") (pintype "passive"))
      (node (ref "LED1") (pin "A") (pinfunction "A_A") (pintype "passive"))
      (node (ref "LED2") (pin "A") (pinfunction "A_A") (pintype "passive"))
    )
    (net (code "54") (name "Net-(L4-Pad2)") (class "Default")
      (node (ref "L4") (pin "2") (pinfunction "2_2") (pintype "passive"))
      (node (ref "R10") (pin "1") (pinfunction "1_1") (pintype "passive"))
    )
    (net (code "55") (name "Net-(LED1-PadC)") (class "Default")
      (node (ref "LED1") (pin "C") (pinfunction "C_C") (pintype "passive"))
      (node (ref "R18") (pin "2") (pinfunction "2_2") (pintype "passive"))
    )
    (net (code "56") (name "Net-(LED2-PadC)") (class "Default")
      (node (ref "LED2") (pin "C") (pinfunction "C_C") (pintype "passive"))
      (node (ref "R17") (pin "2") (pinfunction "2_2") (pintype "passive"))
    )
    (net (code "57") (name "Net-(LED3-PadA)") (class "Default")
      (node (ref "LED3") (pin "A") (pinfunction "A_A") (pintype "passive"))
      (node (ref "R21") (pin "1") (pinfunction "1_1") (pintype "passive"))
    )
    (net (code "58") (name "Net-(P1-Pad1)") (class "Default")
      (node (ref "P1") (pin "1") (pinfunction "1_1") (pintype "passive"))
      (node (ref "R9") (pin "2") (pinfunction "2_2") (pintype "passive"))
    )
    (net (code "59") (name "Net-(P1AA-1)") (class "Default")
      (node (ref "C18") (pin "2") (pinfunction "2_2") (pintype "passive"))
      (node (ref "P1") (pin "33") (pinfunction "1_33") (pintype "passive"))
    )
    (net (code "60") (name "Net-(P1AB-1)") (class "Default")
      (node (ref "C9") (pin "2") (pinfunction "2_2") (pintype "passive"))
      (node (ref "P1") (pin "34") (pinfunction "1_34") (pintype "passive"))
    )
    (net (code "61") (name "Net-(P1AC-1)") (class "Default")
      (node (ref "C17") (pin "2") (pinfunction "2_2") (pintype "passive"))
      (node (ref "P1") (pin "35") (pinfunction "1_35") (pintype "passive"))
    )
    (net (code "62") (name "Net-(P1AD-1)") (class "Default")
      (node (ref "C8") (pin "2") (pinfunction "2_2") (pintype "passive"))
      (node (ref "P1") (pin "36") (pinfunction "1_36") (pintype "passive"))
    )
    (net (code "63") (name "Net-(P1AQ-1)") (class "Default")
      (node (ref "P1") (pin "48") (pinfunction "1_48") (pintype "passive"))
      (node (ref "R8") (pin "2") (pinfunction "2_2") (pintype "passive"))
    )
    (net (code "64") (name "Net-(P1AR-1)") (class "Default")
      (node (ref "C15") (pin "2") (pinfunction "2_2") (pintype "passive"))
      (node (ref "P1") (pin "49") (pinfunction "1_49") (pintype "passive"))
    )
    (net (code "65") (name "Net-(P1AS-1)") (class "Default")
      (node (ref "C22") (pin "2") (pinfunction "2_2") (pintype "passive"))
      (node (ref "P1") (pin "5") (pinfunction "1_5") (pintype "passive"))
    )
    (net (code "66") (name "Net-(P1AU-1)") (class "Default")
      (node (ref "C22") (pin "1") (pinfunction "1_1") (pintype "passive"))
      (node (ref "P1") (pin "6") (pinfunction "1_6") (pintype "passive"))
    )
    (net (code "67") (name "Net-(P1AV-1)") (class "Default")
      (node (ref "C14") (pin "2") (pinfunction "2_2") (pintype "passive"))
      (node (ref "P1") (pin "7") (pinfunction "1_7") (pintype "passive"))
    )
    (net (code "68") (name "Net-(P1AW-1)") (class "Default")
      (node (ref "C21") (pin "2") (pinfunction "2_2") (pintype "passive"))
      (node (ref "P1") (pin "8") (pinfunction "1_8") (pintype "passive"))
    )
    (net (code "69") (name "Net-(P1AX-1)") (class "Default")
      (node (ref "C21") (pin "1") (pinfunction "1_1") (pintype "passive"))
      (node (ref "P1") (pin "9") (pinfunction "1_9") (pintype "passive"))
    )
    (net (code "70") (name "Net-(P1B-1)") (class "Default")
      (node (ref "C13") (pin "2") (pinfunction "2_2") (pintype "passive"))
      (node (ref "P1") (pin "10") (pinfunction "1_10") (pintype "passive"))
    )
    (net (code "71") (name "Net-(P1F-1)") (class "Default")
      (node (ref "C12") (pin "2") (pinfunction "2_2") (pintype "passive"))
      (node (ref "P1") (pin "14") (pinfunction "1_14") (pintype "passive"))
    )
    (net (code "72") (name "Net-(P1R-1)") (class "Default")
      (node (ref "P1") (pin "25") (pinfunction "1_25") (pintype "passive"))
      (node (ref "R6") (pin "2") (pinfunction "2_2") (pintype "passive"))
      (node (ref "R7") (pin "2") (pinfunction "2_2") (pintype "passive"))
    )
    (net (code "73") (name "Net-(P1U-1)") (class "Default")
      (node (ref "C20") (pin "2") (pinfunction "2_2") (pintype "passive"))
      (node (ref "P1") (pin "28") (pinfunction "1_28") (pintype "passive"))
    )
    (net (code "74") (name "Net-(P1V-1)") (class "Default")
      (node (ref "C11") (pin "2") (pinfunction "2_2") (pintype "passive"))
      (node (ref "P1") (pin "29") (pinfunction "1_29") (pintype "passive"))
    )
    (net (code "75") (name "Net-(P1Y-1)") (class "Default")
      (node (ref "C19") (pin "2") (pinfunction "2_2") (pintype "passive"))
      (node (ref "P1") (pin "31") (pinfunction "1_31") (pintype "passive"))
    )
    (net (code "76") (name "Net-(P1Z-1)") (class "Default")
      (node (ref "C10") (pin "2") (pinfunction "2_2") (pintype "passive"))
      (node (ref "P1") (pin "32") (pinfunction "1_32") (pintype "passive"))
    )
    (net (code "77") (name "Net-(Q1-D)") (class "Default")
      (node (ref "C3") (pin "2") (pinfunction "2_2") (pintype "passive"))
      (node (ref "D4") (pin "A") (pinfunction "A_A") (pintype "passive"))
      (node (ref "L1") (pin "2") (pinfunction "2_2") (pintype "passive"))
      (node (ref "Q1") (pin "3") (pinfunction "D_3") (pintype "bidirectional"))
    )
    (net (code "78") (name "Net-(Q2-D)") (class "Default")
      (node (ref "D1") (pin "C") (pinfunction "C_C") (pintype "passive"))
      (node (ref "L2") (pin "2") (pinfunction "2_2") (pintype "passive"))
      (node (ref "Q2") (pin "3") (pinfunction "D_3") (pintype "bidirectional"))
    )
    (net (code "79") (name "Net-(Q2-S)") (class "Default")
      (node (ref "C1") (pin "2") (pinfunction "2_2") (pintype "passive"))
      (node (ref "Q2") (pin "2") (pinfunction "S_2") (pintype "bidirectional"))
      (node (ref "R1") (pin "2") (pinfunction "2_2") (pintype "passive"))
    )
    (net (code "80") (name "Net-(Q3-S)") (class "Default")
      (node (ref "C28") (pin "2") (pinfunction "2_2") (pintype "passive"))
      (node (ref "D7") (pin "C") (pinfunction "C_C") (pintype "passive"))
      (node (ref "JP4") (pin "2") (pinfunction "2_2") (pintype "passive"))
      (node (ref "Q3") (pin "2") (pinfunction "S_2") (pintype "passive"))
      (node (ref "R15") (pin "2") (pinfunction "2_2") (pintype "passive"))
    )
    (net (code "81") (name "Net-(R17-Pad1)") (class "Default")
      (node (ref "R17") (pin "1") (pinfunction "1_1") (pintype "passive"))
      (node (ref "U1") (pin "7") (pinfunction "7_7") (pintype "bidirectional"))
    )
    (net (code "82") (name "Net-(R18-Pad1)") (class "Default")
      (node (ref "R18") (pin "1") (pinfunction "1_1") (pintype "passive"))
      (node (ref "U1") (pin "6") (pinfunction "6_6") (pintype "bidirectional"))
    )
    (net (code "83") (name "Net-(R19-Pad2)") (class "Default")
      (node (ref "R19") (pin "2") (pinfunction "2_2") (pintype "passive"))
      (node (ref "U1") (pin "2") (pinfunction "2_2") (pintype "bidirectional"))
    )
    (net (code "84") (name "Net-(U$4-P$3)") (class "Default")
      (node (ref "R30") (pin "2") (pinfunction "2_2") (pintype "passive"))
      (node (ref "U$4") (pin "P$8") (pinfunction "P$3_P$8") (pintype "bidirectional"))
    )
    (net (code "85") (name "Net-(U$4-P$4)") (class "Default")
      (node (ref "R13") (pin "2") (pinfunction "2_2") (pintype "passive"))
      (node (ref "U$4") (pin "P$9") (pinfunction "P$4_P$9") (pintype "bidirectional"))
    )
    (net (code "86") (name "Net-(U$4-P$10)") (class "Default")
      (node (ref "SHLD") (pin "2") (pinfunction "2_2") (pintype "passive"))
      (node (ref "U$4") (pin "P$1") (pinfunction "P$7_P$1") (pintype "bidirectional"))
      (node (ref "U$4") (pin "P$11") (pinfunction "P$8_P$11") (pintype "bidirectional"))
      (node (ref "U$4") (pin "P$2") (pinfunction "P$9_P$2") (pintype "bidirectional"))
      (node (ref "U$4") (pin "P$5") (pinfunction "P$10_P$5") (pintype "bidirectional"))
    )
    (net (code "87") (name "Net-(U2-IN)") (class "Default")
      (node (ref "JP4") (pin "1") (pinfunction "1_1") (pintype "passive"))
      (node (ref "U2") (pin "1") (pinfunction "IN_1") (pintype "power_in"))
    )
    (net (code "88") (name "VBUS") (class "Default")
      (node (ref "C26") (pin "2") (pinfunction "2_2") (pintype "passive"))
      (node (ref "D7") (pin "A") (pinfunction "A_A") (pintype "passive"))
      (node (ref "JP2") (pin "1") (pinfunction "1_1") (pintype "passive"))
      (node (ref "JP5") (pin "1") (pinfunction "1_1") (pintype "passive"))
      (node (ref "Q3") (pin "1") (pinfunction "G_1") (pintype "passive"))
      (node (ref "R14") (pin "2") (pinfunction "2_2") (pintype "passive"))
      (node (ref "R16") (pin "2") (pinfunction "2_2") (pintype "passive"))
      (node (ref "U$4") (pin "P$6") (pinfunction "P$5_P$6") (pintype "bidirectional"))
      (node (ref "U$4") (pin "P$7") (pinfunction "P$2_P$7") (pintype "bidirectional"))
      (node (ref "U1") (pin "4") (pinfunction "4_4") (pintype "bidirectional"))
      (node (ref "U1") (pin "8") (pinfunction "8_8") (pintype "bidirectional"))
    )
    (net (code "89") (name "unconnected-(J4-PAD1-PadNC1)") (class "Default")
      (node (ref "J4") (pin "NC1") (pinfunction "PAD1_NC1") (pintype "bidirectional"))
    )
    (net (code "90") (name "unconnected-(J4-PAD2-PadNC2)") (class "Default")
      (node (ref "J4") (pin "NC2") (pinfunction "PAD2_NC2") (pintype "bidirectional"))
    )
    (net (code "91") (name "unconnected-(J5-PAD1-PadNC1)") (class "Default")
      (node (ref "J5") (pin "NC1") (pinfunction "PAD1_NC1") (pintype "bidirectional"))
    )
    (net (code "92") (name "unconnected-(J5-PAD2-PadNC2)") (class "Default")
      (node (ref "J5") (pin "NC2") (pinfunction "PAD2_NC2") (pintype "bidirectional"))
    )
    (net (code "93") (name "unconnected-(P1AH-1-Pad4)") (class "Default")
      (node (ref "P1") (pin "4") (pinfunction "1_4") (pintype "passive"))
    )
    (net (code "94") (name "unconnected-(P1AM-1-Pad44)") (class "Default")
      (node (ref "P1") (pin "44") (pinfunction "1_44") (pintype "passive"))
    )
    (net (code "95") (name "unconnected-(P1AT-1-Pad50)") (class "Default")
      (node (ref "P1") (pin "50") (pinfunction "1_50") (pintype "passive"))
    )
    (net (code "96") (name "unconnected-(P1D-1-Pad12)") (class "Default")
      (node (ref "P1") (pin "12") (pinfunction "1_12") (pintype "passive"))
    )
    (net (code "97") (name "unconnected-(P1G-1-Pad15)") (class "Default")
      (node (ref "P1") (pin "15") (pinfunction "1_15") (pintype "passive"))
    )
    (net (code "98") (name "unconnected-(P1H-1-Pad16)") (class "Default")
      (node (ref "P1") (pin "16") (pinfunction "1_16") (pintype "passive"))
    )
    (net (code "99") (name "unconnected-(P1I-1-Pad17)") (class "Default")
      (node (ref "P1") (pin "17") (pinfunction "1_17") (pintype "passive"))
    )
    (net (code "100") (name "unconnected-(P1S-1-Pad26)") (class "Default")
      (node (ref "P1") (pin "26") (pinfunction "1_26") (pintype "passive"))
    )
    (net (code "101") (name "unconnected-(P1T-1-Pad27)") (class "Default")
      (node (ref "P1") (pin "27") (pinfunction "1_27") (pintype "passive"))
    )
    (net (code "102") (name "unconnected-(P1W-1-Pad3)") (class "Default")
      (node (ref "P1") (pin "3") (pinfunction "1_3") (pintype "passive"))
    )
    (net (code "103") (name "unconnected-(U2-P4-Pad4)") (class "Default")
      (node (ref "U2") (pin "4") (pinfunction "P4_4") (pintype "bidirectional"))
    )
    (net (code "104") (name "unconnected-(U3-POCI3{slash}IO19-Pad31)") (class "Default")
      (node (ref "U3") (pin "31") (pinfunction "POCI3/IO19_31") (pintype "bidirectional"))
    )
    (net (code "105") (name "unconnected-(U4-P4-Pad4)") (class "Default")
      (node (ref "U4") (pin "4") (pinfunction "P4_4") (pintype "bidirectional"))
    )
  )
)
